# usb_port.net
KiCad netlist of a schematic drawn in Altium Designer
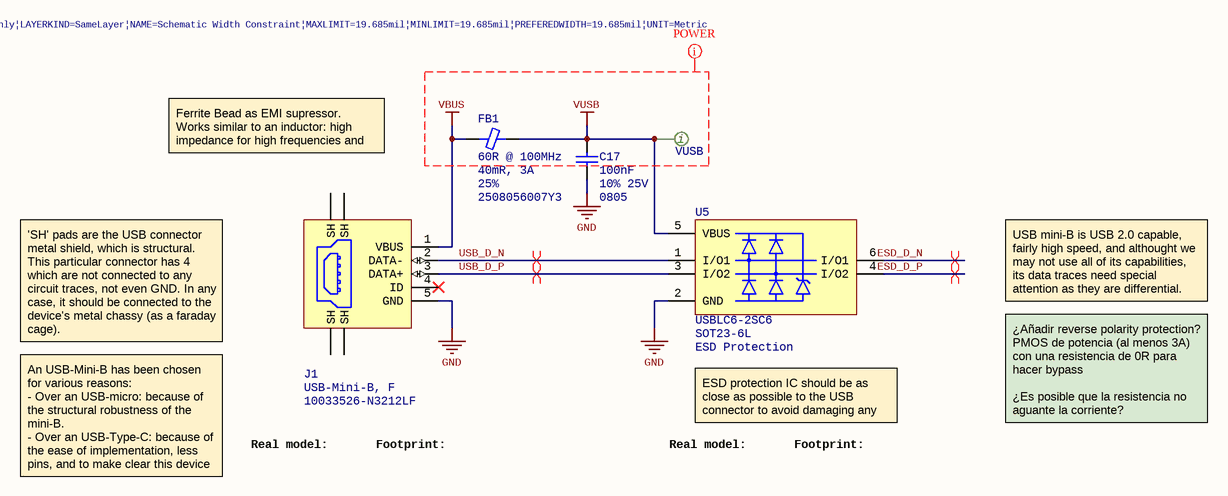
[diagram p0: usb_port.SchDoc]

(export (version "E")
  (design (tool "Eeschema 10.0.6"))
  (components
    (comp (ref "C17")
      (value "100nF")
      (footprint "CAP 0805_2012")
      (description "Ceramic cap size 0805")
      (fields
        (field (name "TOLERANCE") "10% 25V")
        (field (name "PACKAGEDESCRIPTION") "0805")
        (field (name "Comment") "Cap_cer_0805")
      )
      (libsource (lib "tik_handheld_schlib") (part "Cap_cer_0805_100nF_10%"))
    )
    (comp (ref "FB1")
      (value "40mR, 3A")
      (footprint "FER 0805_2012")
      (description "0805, 60Ω, 3A, 25% SMT")
      (fields
        (field (name "DESC") "60R @ 100MHz")
        (field (name "TOLERANCE") "25%")
        (field (name "PART") "2508056007Y3")
        (field (name "Comment") "Ferrite Bead Chip Fair-Rite 2508056007Y3")
      )
      (libsource (lib "tik_handheld_schlib") (part "Ferrite Bead Chip Fair-Rite 2508056007Y3"))
    )
    (comp (ref "J1")
      (value "USB-MINI-B Female")
      (footprint "FCI USB Type B Mini 10033526-N3212LF")
      (description "USB-MINI-B Female, Manufacturer PN/ID: 10033526-N3212LF")
      (fields (field (name "PACKAGEDESCRIPTION") "USB-Mini-B, F") (field (name "PART") "10033526-N3212LF"))
      (libsource (lib "tik_handheld_schlib") (part "CON USB-MINI-B Female"))
    )
    (comp (ref "U5")
      (value "IC USBLC6-2SC6 ESD Prot")
      (footprint "SOT-23-6L USBLC6-2SC6")
      (description "Very low capacitance ESD protection")
      (fields
        (field (name "PART") "USBLC6-2SC6")
        (field (name "PACKAGEDESCRIPTION") "SOT23-6L")
        (field (name "TYPE") "ESD Protection")
      )
      (libsource (lib "tik_handheld_schlib") (part "IC USBLC6-2SC6 ESD Prot"))
    )
    (comp (ref "VUSB")
      (value "Test Point Pad dual sided")
      (footprint "TEST POINT PAD")
      (description "Test point - PCB Pad dual sided")
      (libsource (lib "tik_handheld_schlib") (part "Test Point Pad dual sided"))
    )
  )
  (nets
    (net (code "1") (name "/ESD_D_N") (class "Default")
      (node (ref "U5") (pin "6") (pinfunction "I/O1_6") (pintype "passive"))
    )
    (net (code "2") (name "/ESD_D_P") (class "Default")
      (node (ref "U5") (pin "4") (pinfunction "I/O2_4") (pintype "passive"))
    )
    (net (code "3") (name "/USB_D_N") (class "Default")
      (node (ref "J1") (pin "2") (pinfunction "DATA-_2") (pintype "bidirectional"))
      (node (ref "U5") (pin "1") (pinfunction "I/O1_1") (pintype "passive"))
    )
    (net (code "4") (name "/USB_D_P") (class "Default")
      (node (ref "J1") (pin "3") (pinfunction "DATA+_3") (pintype "bidirectional"))
      (node (ref "U5") (pin "3") (pinfunction "I/O2_3") (pintype "passive"))
    )
    (net (code "5") (name "GND") (class "Default")
      (node (ref "C17") (pin "1") (pinfunction "1_1") (pintype "passive"))
      (node (ref "J1") (pin "5") (pinfunction "GND_5") (pintype "power_in"))
      (node (ref "U5") (pin "2") (pinfunction "GND_2") (pintype "passive"))
    )
    (net (code "6") (name "VBUS") (class "Default")
      (node (ref "FB1") (pin "1") (pinfunction "1_1") (pintype "passive"))
      (node (ref "J1") (pin "1") (pinfunction "VBUS_1") (pintype "power_in"))
    )
    (net (code "7") (name "VUSB") (class "Default")
      (node (ref "C17") (pin "2") (pinfunction "2_2") (pintype "passive"))
      (node (ref "FB1") (pin "2") (pinfunction "2_2") (pintype "passive"))
      (node (ref "U5") (pin "5") (pinfunction "VBUS_5") (pintype "passive"))
      (node (ref "VUSB") (pin "1") (pinfunction "1_1") (pintype "passive"))
    )
    (net (code "8") (name "unconnected-(J1-ID-Pad4)") (class "Default")
      (node (ref "J1") (pin "4") (pinfunction "ID_4") (pintype "passive+no_connect"))
    )
    (net (code "9") (name "unconnected-(J1-SH-Pad6)") (class "Default")
      (node (ref "J1") (pin "6") (pinfunction "SH_6") (pintype "passive"))
    )
    (net (code "10") (name "unconnected-(J1-SH-Pad7)") (class "Default")
      (node (ref "J1") (pin "7") (pinfunction "SH_7") (pintype "passive"))
    )
    (net (code "11") (name "unconnected-(J1-SH-Pad8)") (class "Default")
      (node (ref "J1") (pin "8") (pinfunction "SH_8") (pintype "passive"))
    )
    (net (code "12") (name "unconnected-(J1-SH-Pad9)") (class "Default")
      (node (ref "J1") (pin "9") (pinfunction "SH_9") (pintype "passive"))
    )
  )
)
